# PAC_Attack_RevB.net
KiCad netlist of a schematic drawn in EAGLE
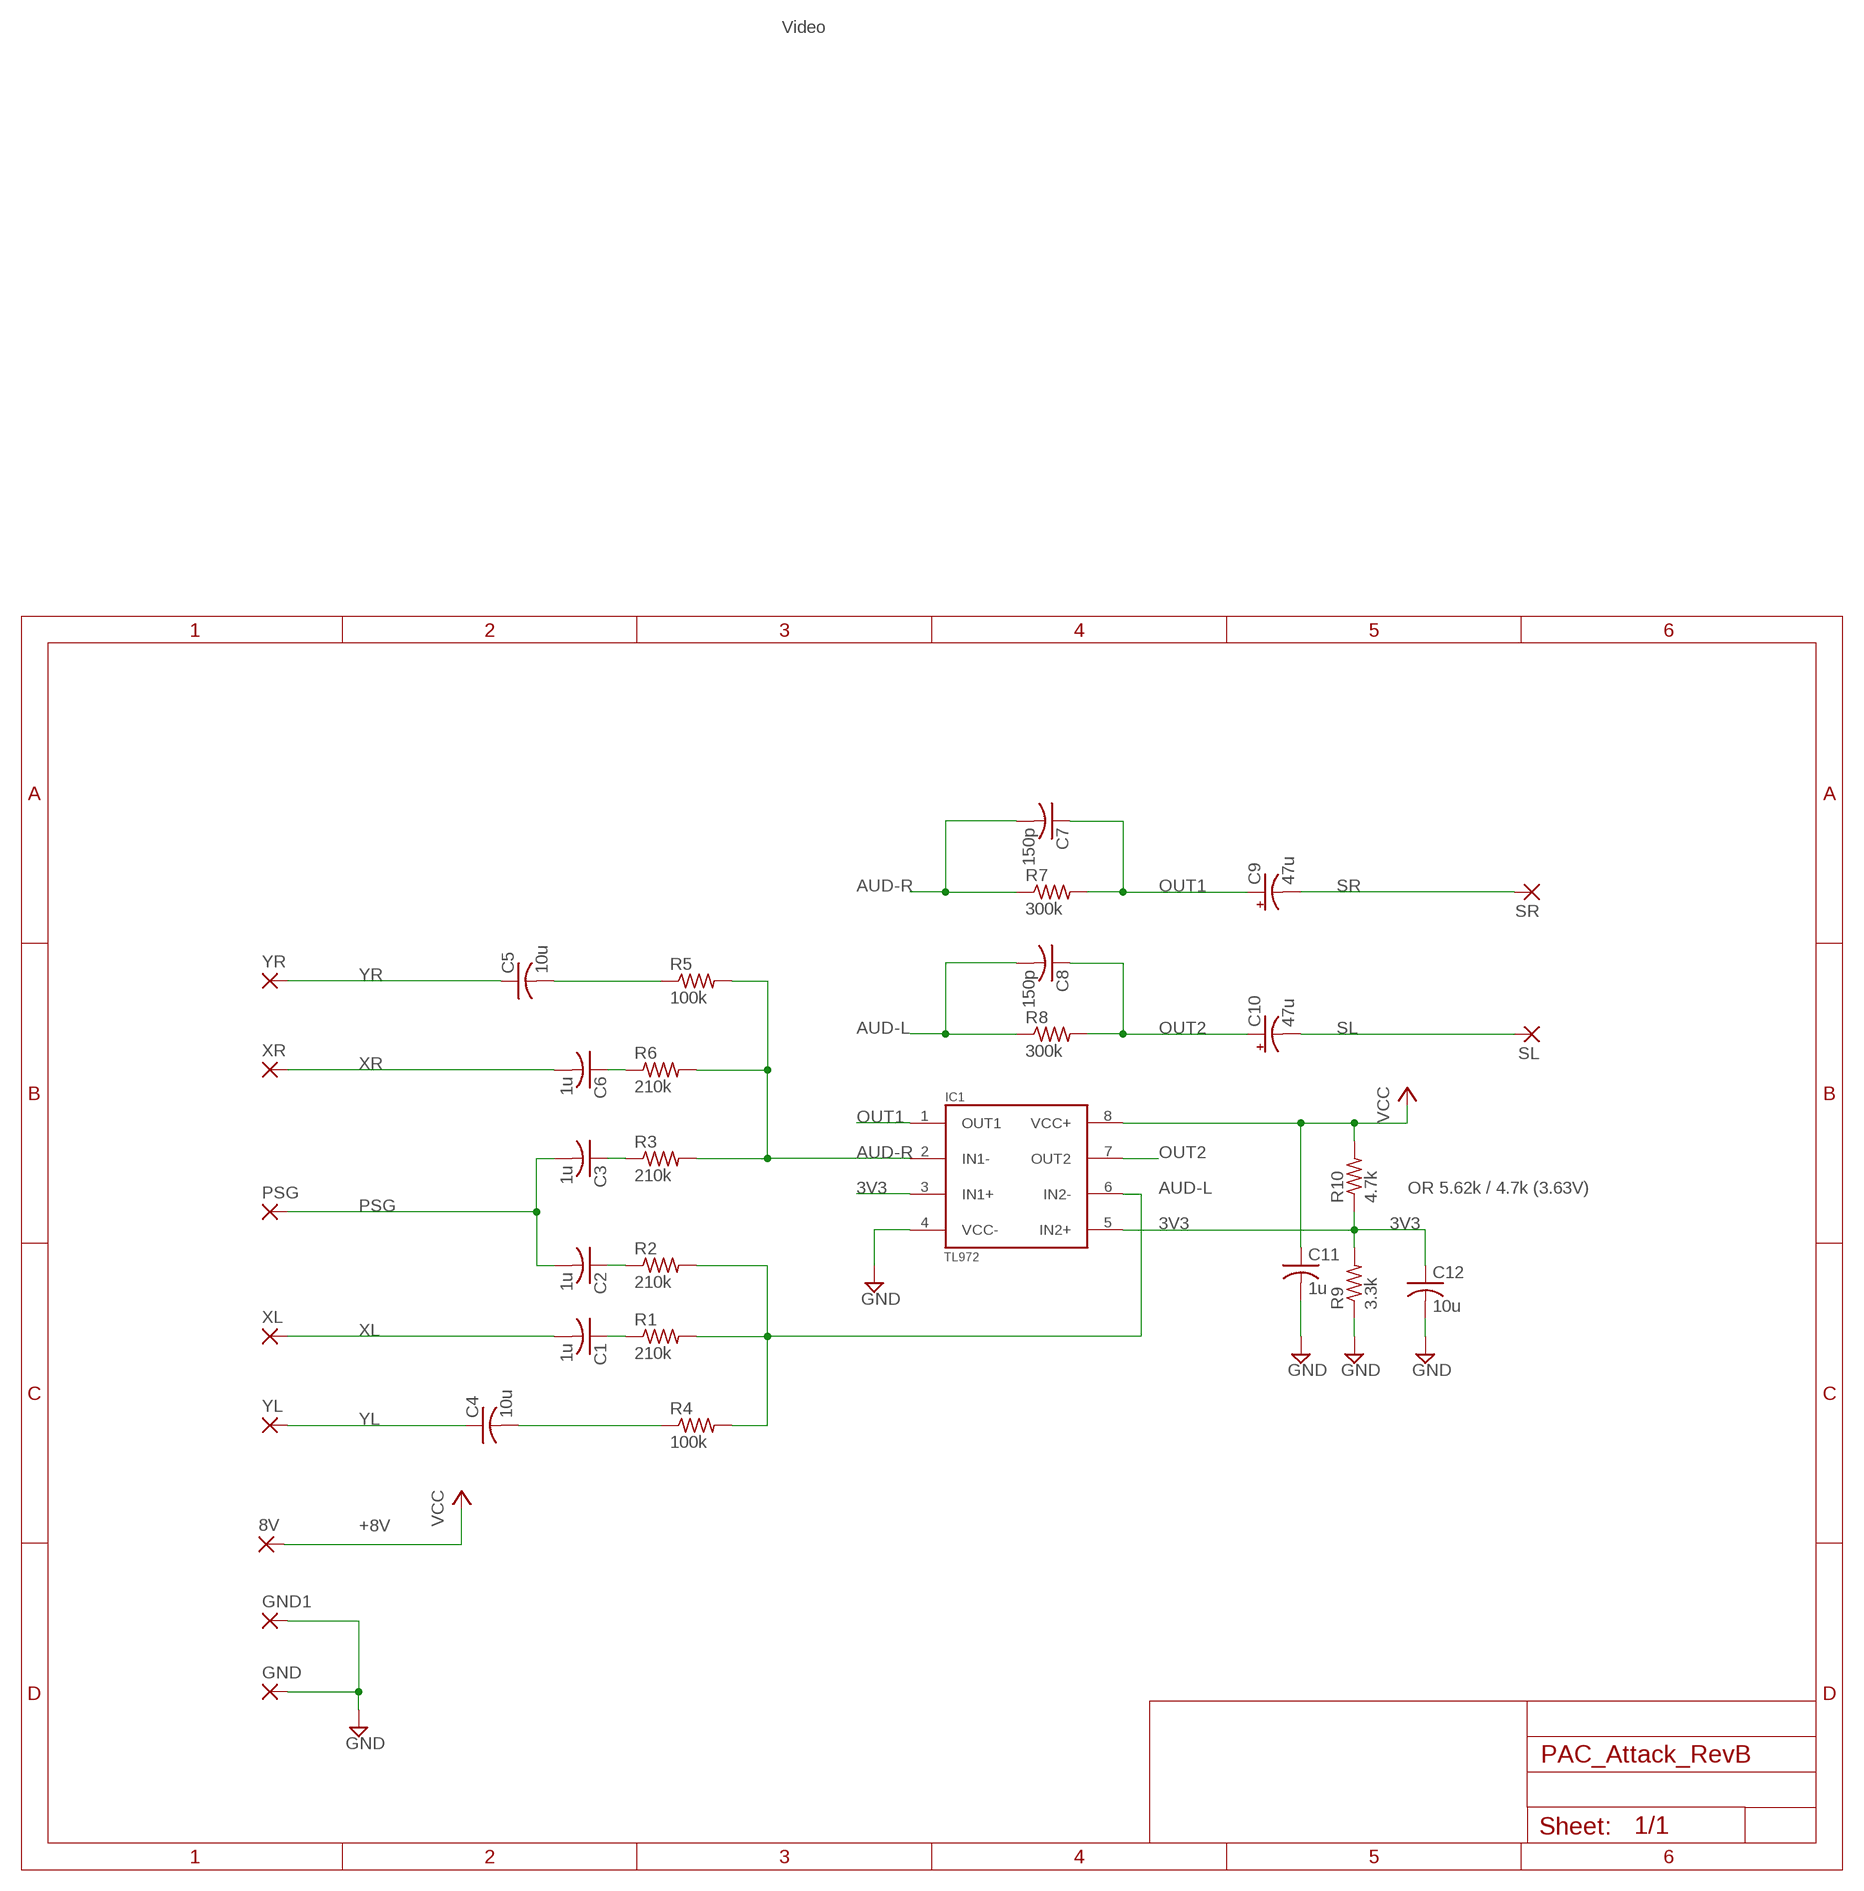
[diagram p0: schematic, sheet 1]

(export (version "E")
  (design (tool "Eeschema 10.0.6"))
  (components
    (comp (ref "8V")
      (value "SMD2")
      (footprint "eagle-import:SMD1,27-2,54")
      (libsource (lib "eagle-import") (part "SMD2"))
    )
    (comp (ref "C1")
      (value "1u")
      (footprint "eagle-import:C0603")
      (libsource (lib "eagle-import") (part "C-USC0603"))
    )
    (comp (ref "C2")
      (value "1u")
      (footprint "eagle-import:C0603")
      (libsource (lib "eagle-import") (part "C-USC0603"))
    )
    (comp (ref "C3")
      (value "1u")
      (footprint "eagle-import:C0603")
      (libsource (lib "eagle-import") (part "C-USC0603"))
    )
    (comp (ref "C4")
      (value "10u")
      (footprint "eagle-import:C0805")
      (libsource (lib "eagle-import") (part "C-USC0805"))
    )
    (comp (ref "C5")
      (value "10u")
      (footprint "eagle-import:C0805")
      (libsource (lib "eagle-import") (part "C-USC0805"))
    )
    (comp (ref "C6")
      (value "1u")
      (footprint "eagle-import:C0603")
      (libsource (lib "eagle-import") (part "C-USC0603"))
    )
    (comp (ref "C7")
      (value "150p")
      (footprint "eagle-import:C0603")
      (libsource (lib "eagle-import") (part "C-USC0603"))
    )
    (comp (ref "C8")
      (value "150p")
      (footprint "eagle-import:C0603")
      (libsource (lib "eagle-import") (part "C-USC0603"))
    )
    (comp (ref "C9")
      (value "47u")
      (footprint "eagle-import:CT3528")
      (libsource (lib "eagle-import") (part "CPOL-USCT3528"))
    )
    (comp (ref "C10")
      (value "47u")
      (footprint "eagle-import:CT3528")
      (libsource (lib "eagle-import") (part "CPOL-USCT3528"))
    )
    (comp (ref "C11")
      (value "1u")
      (footprint "eagle-import:C0603")
      (libsource (lib "eagle-import") (part "C-USC0603"))
    )
    (comp (ref "C12")
      (value "10u")
      (footprint "eagle-import:C1206")
      (libsource (lib "eagle-import") (part "C-USC1206"))
    )
    (comp (ref "GND")
      (value "SMD2")
      (footprint "eagle-import:SMD1,27-2,54")
      (libsource (lib "eagle-import") (part "SMD2"))
    )
    (comp (ref "GND1")
      (value "SMD2")
      (footprint "eagle-import:SMD1,27-2,54")
      (libsource (lib "eagle-import") (part "SMD2"))
    )
    (comp (ref "IC1")
      (value "TL972")
      (footprint "eagle-import:SOIC8")
      (libsource (lib "eagle-import") (part "TL972"))
    )
    (comp (ref "PSG")
      (value "SMD2")
      (footprint "eagle-import:SMD1,27-2,54")
      (libsource (lib "eagle-import") (part "SMD2"))
    )
    (comp (ref "R1")
      (value "210k")
      (footprint "eagle-import:R0603")
      (libsource (lib "eagle-import") (part "R-US_R0603"))
    )
    (comp (ref "R2")
      (value "210k")
      (footprint "eagle-import:R0603")
      (libsource (lib "eagle-import") (part "R-US_R0603"))
    )
    (comp (ref "R3")
      (value "210k")
      (footprint "eagle-import:R0603")
      (libsource (lib "eagle-import") (part "R-US_R0603"))
    )
    (comp (ref "R4")
      (value "100k")
      (footprint "eagle-import:R0603")
      (libsource (lib "eagle-import") (part "R-US_R0603"))
    )
    (comp (ref "R5")
      (value "100k")
      (footprint "eagle-import:R0603")
      (libsource (lib "eagle-import") (part "R-US_R0603"))
    )
    (comp (ref "R6")
      (value "210k")
      (footprint "eagle-import:R0603")
      (libsource (lib "eagle-import") (part "R-US_R0603"))
    )
    (comp (ref "R7")
      (value "300k")
      (footprint "eagle-import:R0603")
      (libsource (lib "eagle-import") (part "R-US_R0603"))
    )
    (comp (ref "R8")
      (value "300k")
      (footprint "eagle-import:R0603")
      (libsource (lib "eagle-import") (part "R-US_R0603"))
    )
    (comp (ref "R9")
      (value "3.3k")
      (footprint "eagle-import:R0603")
      (libsource (lib "eagle-import") (part "R-US_R0603"))
    )
    (comp (ref "R10")
      (value "4.7k")
      (footprint "eagle-import:R0603")
      (libsource (lib "eagle-import") (part "R-US_R0603"))
    )
    (comp (ref "SL")
      (value "SMD2")
      (footprint "eagle-import:SMD1,27-2,54")
      (libsource (lib "eagle-import") (part "SMD2"))
    )
    (comp (ref "SR")
      (value "SMD2")
      (footprint "eagle-import:SMD1,27-2,54")
      (libsource (lib "eagle-import") (part "SMD2"))
    )
    (comp (ref "XL")
      (value "SMD2")
      (footprint "eagle-import:SMD1,27-2,54")
      (libsource (lib "eagle-import") (part "SMD2"))
    )
    (comp (ref "XR")
      (value "SMD2")
      (footprint "eagle-import:SMD1,27-2,54")
      (libsource (lib "eagle-import") (part "SMD2"))
    )
    (comp (ref "YL")
      (value "SMD2")
      (footprint "eagle-import:SMD1,27-2,54")
      (libsource (lib "eagle-import") (part "SMD2"))
    )
    (comp (ref "YR")
      (value "SMD2")
      (footprint "eagle-import:SMD1,27-2,54")
      (libsource (lib "eagle-import") (part "SMD2"))
    )
  )
  (nets
    (net (code "1") (name "/3V3") (class "Default")
      (node (ref "C12") (pin "1") (pinfunction "1_1") (pintype "passive"))
      (node (ref "IC1") (pin "3") (pinfunction "IN1+_3") (pintype "bidirectional"))
      (node (ref "IC1") (pin "5") (pinfunction "IN2+_5") (pintype "bidirectional"))
      (node (ref "R10") (pin "1") (pinfunction "1_1") (pintype "passive"))
      (node (ref "R9") (pin "2") (pinfunction "2_2") (pintype "passive"))
    )
    (net (code "2") (name "/AUD-L") (class "Default")
      (node (ref "C8") (pin "2") (pinfunction "2_2") (pintype "passive"))
      (node (ref "IC1") (pin "6") (pinfunction "IN2-_6") (pintype "bidirectional"))
      (node (ref "R1") (pin "2") (pinfunction "2_2") (pintype "passive"))
      (node (ref "R2") (pin "2") (pinfunction "2_2") (pintype "passive"))
      (node (ref "R4") (pin "2") (pinfunction "2_2") (pintype "passive"))
      (node (ref "R8") (pin "1") (pinfunction "1_1") (pintype "passive"))
    )
    (net (code "3") (name "/AUD-R") (class "Default")
      (node (ref "C7") (pin "2") (pinfunction "2_2") (pintype "passive"))
      (node (ref "IC1") (pin "2") (pinfunction "IN1-_2") (pintype "bidirectional"))
      (node (ref "R3") (pin "2") (pinfunction "2_2") (pintype "passive"))
      (node (ref "R5") (pin "2") (pinfunction "2_2") (pintype "passive"))
      (node (ref "R6") (pin "2") (pinfunction "2_2") (pintype "passive"))
      (node (ref "R7") (pin "1") (pinfunction "1_1") (pintype "passive"))
    )
    (net (code "4") (name "/OUT1") (class "Default")
      (node (ref "C7") (pin "1") (pinfunction "1_1") (pintype "passive"))
      (node (ref "C9") (pin "+") (pinfunction "+_+") (pintype "passive"))
      (node (ref "IC1") (pin "1") (pinfunction "OUT1_1") (pintype "bidirectional"))
      (node (ref "R7") (pin "2") (pinfunction "2_2") (pintype "passive"))
    )
    (net (code "5") (name "/OUT2") (class "Default")
      (node (ref "C10") (pin "+") (pinfunction "+_+") (pintype "passive"))
      (node (ref "C8") (pin "1") (pinfunction "1_1") (pintype "passive"))
      (node (ref "IC1") (pin "7") (pinfunction "OUT2_7") (pintype "bidirectional"))
      (node (ref "R8") (pin "2") (pinfunction "2_2") (pintype "passive"))
    )
    (net (code "6") (name "/PSG") (class "Default")
      (node (ref "C2") (pin "2") (pinfunction "2_2") (pintype "passive"))
      (node (ref "C3") (pin "2") (pinfunction "2_2") (pintype "passive"))
      (node (ref "PSG") (pin "1") (pinfunction "P_1") (pintype "passive"))
    )
    (net (code "7") (name "/SL") (class "Default")
      (node (ref "C10") (pin "-") (pinfunction "-_-") (pintype "passive"))
      (node (ref "SL") (pin "1") (pinfunction "P_1") (pintype "passive"))
    )
    (net (code "8") (name "/SR") (class "Default")
      (node (ref "C9") (pin "-") (pinfunction "-_-") (pintype "passive"))
      (node (ref "SR") (pin "1") (pinfunction "P_1") (pintype "passive"))
    )
    (net (code "9") (name "/XL") (class "Default")
      (node (ref "C1") (pin "2") (pinfunction "2_2") (pintype "passive"))
      (node (ref "XL") (pin "1") (pinfunction "P_1") (pintype "passive"))
    )
    (net (code "10") (name "/XR") (class "Default")
      (node (ref "C6") (pin "2") (pinfunction "2_2") (pintype "passive"))
      (node (ref "XR") (pin "1") (pinfunction "P_1") (pintype "passive"))
    )
    (net (code "11") (name "/YL") (class "Default")
      (node (ref "C4") (pin "1") (pinfunction "1_1") (pintype "passive"))
      (node (ref "YL") (pin "1") (pinfunction "P_1") (pintype "passive"))
    )
    (net (code "12") (name "/YR") (class "Default")
      (node (ref "C5") (pin "1") (pinfunction "1_1") (pintype "passive"))
      (node (ref "YR") (pin "1") (pinfunction "P_1") (pintype "passive"))
    )
    (net (code "13") (name "GND") (class "Default")
      (node (ref "C11") (pin "2") (pinfunction "2_2") (pintype "passive"))
      (node (ref "C12") (pin "2") (pinfunction "2_2") (pintype "passive"))
      (node (ref "GND") (pin "1") (pinfunction "P_1") (pintype "passive"))
      (node (ref "GND1") (pin "1") (pinfunction "P_1") (pintype "passive"))
      (node (ref "IC1") (pin "4") (pinfunction "VCC-_4") (pintype "bidirectional"))
      (node (ref "R9") (pin "1") (pinfunction "1_1") (pintype "passive"))
    )
    (net (code "14") (name "Net-(C1-Pad1)") (class "Default")
      (node (ref "C1") (pin "1") (pinfunction "1_1") (pintype "passive"))
      (node (ref "R1") (pin "1") (pinfunction "1_1") (pintype "passive"))
    )
    (net (code "15") (name "Net-(C2-Pad1)") (class "Default")
      (node (ref "C2") (pin "1") (pinfunction "1_1") (pintype "passive"))
      (node (ref "R2") (pin "1") (pinfunction "1_1") (pintype "passive"))
    )
    (net (code "16") (name "Net-(C3-Pad1)") (class "Default")
      (node (ref "C3") (pin "1") (pinfunction "1_1") (pintype "passive"))
      (node (ref "R3") (pin "1") (pinfunction "1_1") (pintype "passive"))
    )
    (net (code "17") (name "Net-(C4-Pad2)") (class "Default")
      (node (ref "C4") (pin "2") (pinfunction "2_2") (pintype "passive"))
      (node (ref "R4") (pin "1") (pinfunction "1_1") (pintype "passive"))
    )
    (net (code "18") (name "Net-(C5-Pad2)") (class "Default")
      (node (ref "C5") (pin "2") (pinfunction "2_2") (pintype "passive"))
      (node (ref "R5") (pin "1") (pinfunction "1_1") (pintype "passive"))
    )
    (net (code "19") (name "Net-(C6-Pad1)") (class "Default")
      (node (ref "C6") (pin "1") (pinfunction "1_1") (pintype "passive"))
      (node (ref "R6") (pin "1") (pinfunction "1_1") (pintype "passive"))
    )
    (net (code "20") (name "VCC") (class "Default")
      (node (ref "8V") (pin "1") (pinfunction "P_1") (pintype "passive"))
      (node (ref "C11") (pin "1") (pinfunction "1_1") (pintype "passive"))
      (node (ref "IC1") (pin "8") (pinfunction "VCC+_8") (pintype "bidirectional"))
      (node (ref "R10") (pin "2") (pinfunction "2_2") (pintype "passive"))
    )
  )
)
